# eeZee_tiny.net
KiCad netlist of a schematic drawn in EAGLE
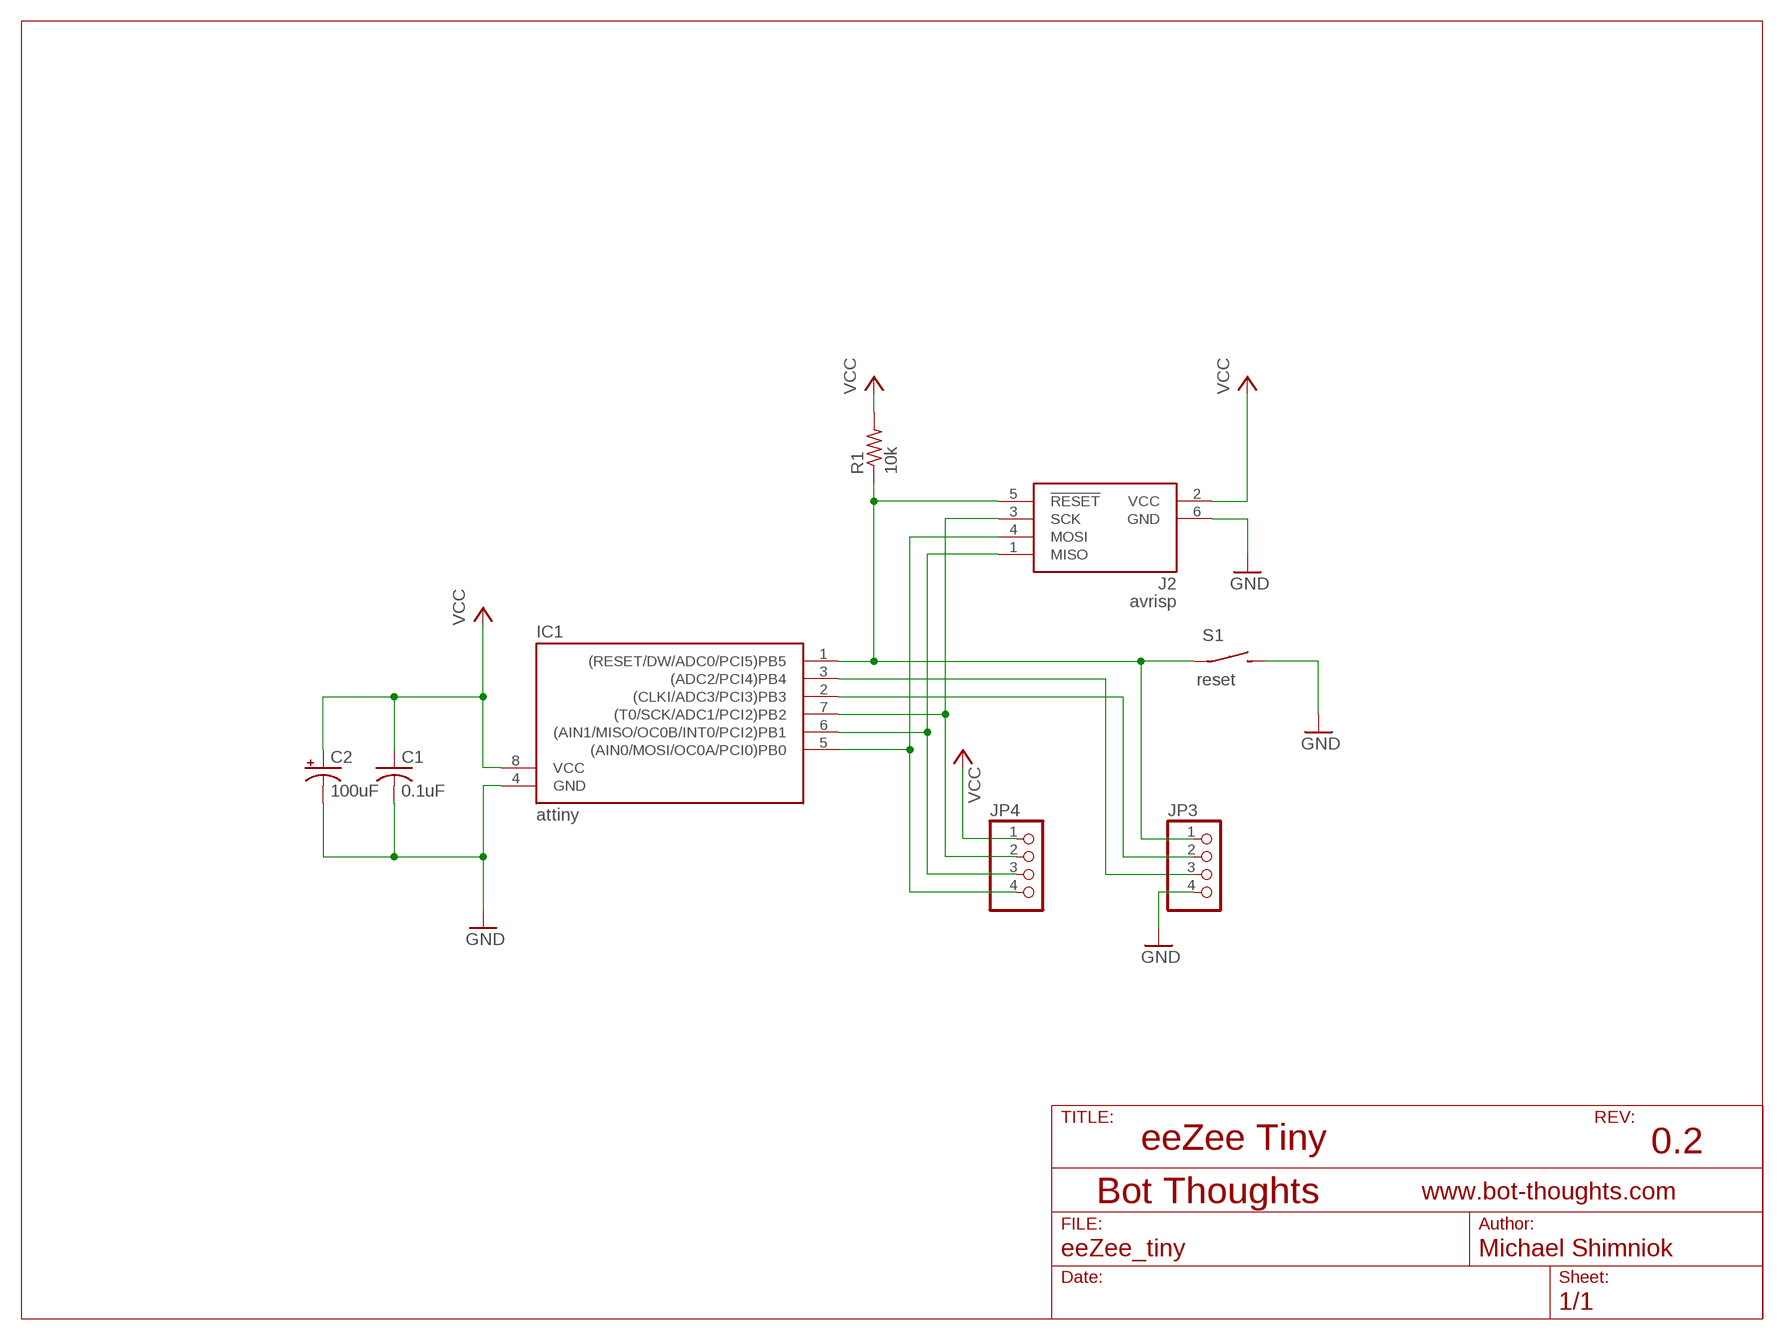
[diagram p0: schematic, sheet 1]

(export (version "E")
  (design (tool "Eeschema 10.0.6"))
  (components
    (comp (ref "C1")
      (value "0.1uF")
      (footprint "eagle-import:C0603")
      (fields (field (name "PARTNO") "0603YC104KAT2A"))
      (libsource (lib "eagle-import") (part "C-USC0603"))
    )
    (comp (ref "C2")
      (value "100uF")
      (footprint "eagle-import:SMC_B")
      (fields (field (name "PARTNO") "F930J107MBA"))
      (libsource (lib "eagle-import") (part "CPOL-USSMCB"))
    )
    (comp (ref "IC1")
      (value "attiny")
      (footprint "eagle-import:DIL08")
      (fields (field (name "PARTNO") "A08-LC-TT-R"))
      (libsource (lib "eagle-import") (part "ATTINY13P-20"))
    )
    (comp (ref "J2")
      (value "avrisp")
      (footprint "eagle-import:CON6P2R")
      (libsource (lib "eagle-import") (part "AVRISP6"))
    )
    (comp (ref "JP3")
      (value "PINHD-1X04_2.54-S")
      (footprint "eagle-import:1X04-S")
      (libsource (lib "eagle-import") (part "PINHD-1X04_2.54-S"))
    )
    (comp (ref "JP4")
      (value "PINHD-1X04_2.54-S")
      (footprint "eagle-import:1X04-S")
      (libsource (lib "eagle-import") (part "PINHD-1X04_2.54-S"))
    )
    (comp (ref "R1")
      (value "10k")
      (footprint "eagle-import:R0603")
      (fields (field (name "PARTNO") "ERJ-3GEYJ103V"))
      (libsource (lib "eagle-import") (part "R-US_R0603"))
    )
    (comp (ref "S1")
      (value "reset")
      (footprint "eagle-import:6MMTACTILE_RECT")
      (libsource (lib "eagle-import") (part "SPST_TAC_RECT1"))
    )
  )
  (nets
    (net (code "1") (name "GND") (class "Default")
      (node (ref "C1") (pin "2") (pinfunction "2_2") (pintype "passive"))
      (node (ref "C2") (pin "-") (pinfunction "-_-") (pintype "passive"))
      (node (ref "IC1") (pin "4") (pinfunction "GND_4") (pintype "power_in"))
      (node (ref "J2") (pin "6") (pinfunction "GND_6") (pintype "power_in"))
      (node (ref "JP3") (pin "4") (pinfunction "4_4") (pintype "passive"))
      (node (ref "S1") (pin "P$2") (pinfunction "S_P$2") (pintype "passive"))
    )
    (net (code "2") (name "Net-(IC1-(ADC2{slash}PCI4)PB4)") (class "Default")
      (node (ref "IC1") (pin "3") (pinfunction "(ADC2/PCI4)PB4_3") (pintype "bidirectional"))
      (node (ref "JP3") (pin "3") (pinfunction "3_3") (pintype "passive"))
    )
    (net (code "3") (name "Net-(IC1-(AIN0{slash}MOSI{slash}OC0A{slash}PCI0)PB0)") (class "Default")
      (node (ref "IC1") (pin "5") (pinfunction "(AIN0/MOSI/OC0A/PCI0)PB0_5") (pintype "bidirectional"))
      (node (ref "J2") (pin "4") (pinfunction "MOSI_4") (pintype "output"))
      (node (ref "JP4") (pin "4") (pinfunction "4_4") (pintype "passive"))
    )
    (net (code "4") (name "Net-(IC1-(AIN1{slash}MISO{slash}OC0B{slash}INT0{slash}PCI2)PB1)") (class "Default")
      (node (ref "IC1") (pin "6") (pinfunction "(AIN1/MISO/OC0B/INT0/PCI2)PB1_6") (pintype "bidirectional"))
      (node (ref "J2") (pin "1") (pinfunction "MISO_1") (pintype "input"))
      (node (ref "JP4") (pin "3") (pinfunction "3_3") (pintype "passive"))
    )
    (net (code "5") (name "Net-(IC1-(CLKI{slash}ADC3{slash}PCI3)PB3)") (class "Default")
      (node (ref "IC1") (pin "2") (pinfunction "(CLKI/ADC3/PCI3)PB3_2") (pintype "bidirectional"))
      (node (ref "JP3") (pin "2") (pinfunction "2_2") (pintype "passive"))
    )
    (net (code "6") (name "Net-(IC1-(RESET{slash}DW{slash}ADC0{slash}PCI5)PB5)") (class "Default")
      (node (ref "IC1") (pin "1") (pinfunction "(RESET/DW/ADC0/PCI5)PB5_1") (pintype "bidirectional"))
      (node (ref "J2") (pin "5") (pinfunction "~{RESET}_5") (pintype "output"))
      (node (ref "JP3") (pin "1") (pinfunction "1_1") (pintype "passive"))
      (node (ref "R1") (pin "1") (pinfunction "1_1") (pintype "passive"))
      (node (ref "S1") (pin "P$1") (pinfunction "P_P$1") (pintype "passive"))
    )
    (net (code "7") (name "Net-(IC1-(T0{slash}SCK{slash}ADC1{slash}PCI2)PB2)") (class "Default")
      (node (ref "IC1") (pin "7") (pinfunction "(T0/SCK/ADC1/PCI2)PB2_7") (pintype "bidirectional"))
      (node (ref "J2") (pin "3") (pinfunction "SCK_3") (pintype "output"))
      (node (ref "JP4") (pin "2") (pinfunction "2_2") (pintype "passive"))
    )
    (net (code "8") (name "VCC") (class "Default")
      (node (ref "C1") (pin "1") (pinfunction "1_1") (pintype "passive"))
      (node (ref "C2") (pin "+") (pinfunction "+_+") (pintype "passive"))
      (node (ref "IC1") (pin "8") (pinfunction "VCC_8") (pintype "power_in"))
      (node (ref "J2") (pin "2") (pinfunction "VCC_2") (pintype "power_in"))
      (node (ref "JP4") (pin "1") (pinfunction "1_1") (pintype "passive"))
      (node (ref "R1") (pin "2") (pinfunction "2_2") (pintype "passive"))
    )
  )
)
